# Power.net
KiCad netlist of a schematic drawn in Altium Designer
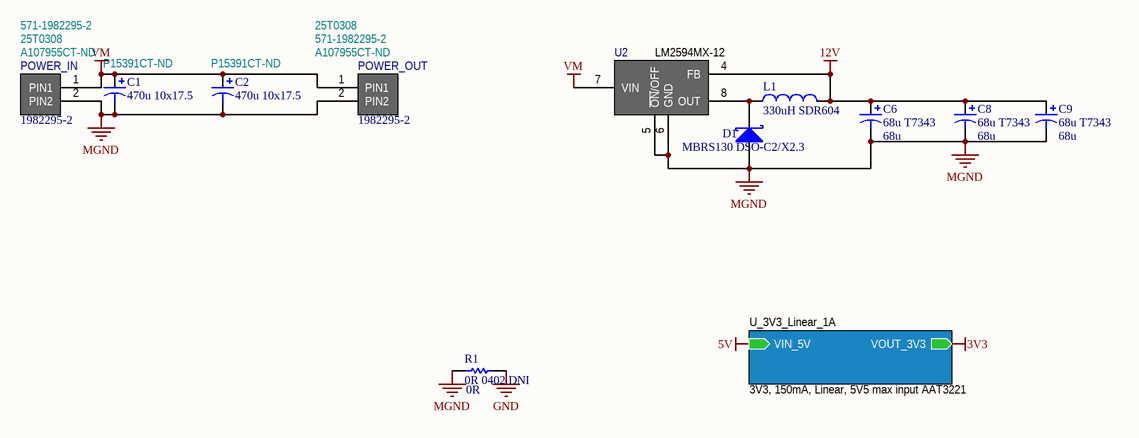
[diagram p0: Power.SchDoc]

(export (version "E")
  (design (tool "Eeschema 10.0.6"))
  (components
    (comp (ref "C1")
      (value "470u 10x17.5")
      (footprint "CAPPR5-10x17.5")
      (description "Polarized Capacitor (Radial)")
      (fields
        (field (name "SUPPLIER PART NUMBER 1") "P15391CT-ND")
        (field (name "PUBLISHER") "Altium Limited")
      )
      (libsource (lib "Miscellaneous Devices") (part "Cap Pol1"))
    )
    (comp (ref "C2")
      (value "470u 10x17.5")
      (footprint "CAPPR5-10x17.5")
      (description "Polarized Capacitor (Radial)")
      (fields
        (field (name "SUPPLIER PART NUMBER 1") "P15391CT-ND")
        (field (name "PUBLISHER") "Altium Limited")
      )
      (libsource (lib "Miscellaneous Devices") (part "Cap Pol1"))
    )
    (comp (ref "C6")
      (value "68u T7343")
      (footprint "TC7343-2917")
      (description "Polarized Capacitor (Radial)")
      (fields (field (name "ALTIUM_VALUE") "68u") (field (name "PUBLISHER") "Altium Limited"))
      (libsource (lib "Miscellaneous Devices") (part "Cap Pol1"))
    )
    (comp (ref "C8")
      (value "68u T7343")
      (footprint "TC7343-2917")
      (description "Polarized Capacitor (Radial)")
      (fields (field (name "ALTIUM_VALUE") "68u") (field (name "PUBLISHER") "Altium Limited"))
      (libsource (lib "Miscellaneous Devices") (part "Cap Pol1"))
    )
    (comp (ref "C9")
      (value "68u T7343")
      (footprint "TC7343-2917")
      (description "Polarized Capacitor (Radial)")
      (fields (field (name "ALTIUM_VALUE") "68u") (field (name "PUBLISHER") "Altium Limited"))
      (libsource (lib "Miscellaneous Devices") (part "Cap Pol1"))
    )
    (comp (ref "D1")
      (value "MBRS130 DSO-C2/X2.3")
      (footprint "DSO-C2/X2.3")
      (description "Schottky Diode")
      (fields (field (name "PUBLISHER") "Altium Limited"))
      (libsource (lib "Miscellaneous Devices") (part "D Schottky"))
    )
    (comp (ref "L1")
      (value "330uH SDR604")
      (footprint "SDR604")
      (description "Inductor")
      (fields (field (name "PUBLISHER") "Altium Limited"))
      (libsource (lib "Miscellaneous Devices") (part "Inductor"))
    )
    (comp (ref "POWER_IN")
      (value "1982295-2")
      (footprint "1982295-2")
      (fields
        (field (name "SUPPLIER PART NUMBER 1") "A107955CT-ND")
        (field (name "SUPPLIER PART NUMBER 2") "25T0308")
        (field (name "SUPPLIER PART NUMBER 3") "571-1982295-2")
      )
      (libsource (lib "") (part "1982295-2_1"))
    )
    (comp (ref "POWER_OUT")
      (value "1982295-2")
      (footprint "1982295-2")
      (fields
        (field (name "SUPPLIER PART NUMBER 1") "A107955CT-ND")
        (field (name "SUPPLIER PART NUMBER 2") "571-1982295-2")
        (field (name "SUPPLIER PART NUMBER 3") "25T0308")
      )
      (libsource (lib "TE Connectivity") (part "1982295-2"))
    )
    (comp (ref "R1")
      (value "0R 0402 DNI")
      (footprint "RESC2012N")
      (description "Semiconductor Resistor")
      (fields (field (name "ALTIUM_VALUE") "0R") (field (name "PUBLISHER") "Altium Limited"))
      (libsource (lib "Miscellaneous Devices") (part "Res Semi"))
    )
    (comp (ref "U2")
      (value "LM2594MX-12")
      (footprint "SOIC127P600-8CN")
      (libsource (lib "TI Power Mgt Voltage Regulator Custom") (part "LM2594MX-12"))
    )
  )
  (nets
    (net (code "3") (name "12V") (class "Default")
      (node (ref "C6") (pin "1") (pinfunction "1_1") (pintype "passive"))
      (node (ref "C8") (pin "1") (pinfunction "1_1") (pintype "passive"))
      (node (ref "C9") (pin "1") (pinfunction "1_1") (pintype "passive"))
      (node (ref "L1") (pin "2") (pinfunction "2_2") (pintype "passive"))
      (node (ref "U2") (pin "4") (pinfunction "FB_4") (pintype "power_in"))
    )
    (net (code "4") (name "GND") (class "Default")
      (node (ref "R1") (pin "1") (pinfunction "1_1") (pintype "passive"))
    )
    (net (code "5") (name "MGND") (class "Default")
      (node (ref "C1") (pin "2") (pinfunction "2_2") (pintype "passive"))
      (node (ref "C2") (pin "2") (pinfunction "2_2") (pintype "passive"))
      (node (ref "C6") (pin "2") (pinfunction "2_2") (pintype "passive"))
      (node (ref "C8") (pin "2") (pinfunction "2_2") (pintype "passive"))
      (node (ref "C9") (pin "2") (pinfunction "2_2") (pintype "passive"))
      (node (ref "D1") (pin "1") (pinfunction "A_1") (pintype "passive"))
      (node (ref "POWER_IN") (pin "2") (pinfunction "PIN2_2") (pintype "power_in"))
      (node (ref "POWER_OUT") (pin "2") (pinfunction "PIN2_2") (pintype "power_in"))
      (node (ref "R1") (pin "2") (pinfunction "2_2") (pintype "passive"))
      (node (ref "U2") (pin "5") (pinfunction "~{ON}/OFF_5") (pintype "power_in"))
      (node (ref "U2") (pin "6") (pinfunction "GND_6") (pintype "power_in"))
    )
    (net (code "6") (name "Net-(D1-K)") (class "Default")
      (node (ref "D1") (pin "2") (pinfunction "K_2") (pintype "passive"))
      (node (ref "L1") (pin "1") (pinfunction "1_1") (pintype "passive"))
      (node (ref "U2") (pin "8") (pinfunction "OUT_8") (pintype "power_in"))
    )
    (net (code "7") (name "VM") (class "Default")
      (node (ref "C1") (pin "1") (pinfunction "1_1") (pintype "passive"))
      (node (ref "C2") (pin "1") (pinfunction "1_1") (pintype "passive"))
      (node (ref "POWER_IN") (pin "1") (pinfunction "PIN1_1") (pintype "power_in"))
      (node (ref "POWER_OUT") (pin "1") (pinfunction "PIN1_1") (pintype "power_in"))
      (node (ref "U2") (pin "7") (pinfunction "VIN_7") (pintype "power_in"))
    )
  )
)
